# MCU.net
KiCad netlist of a schematic drawn in Altium Designer
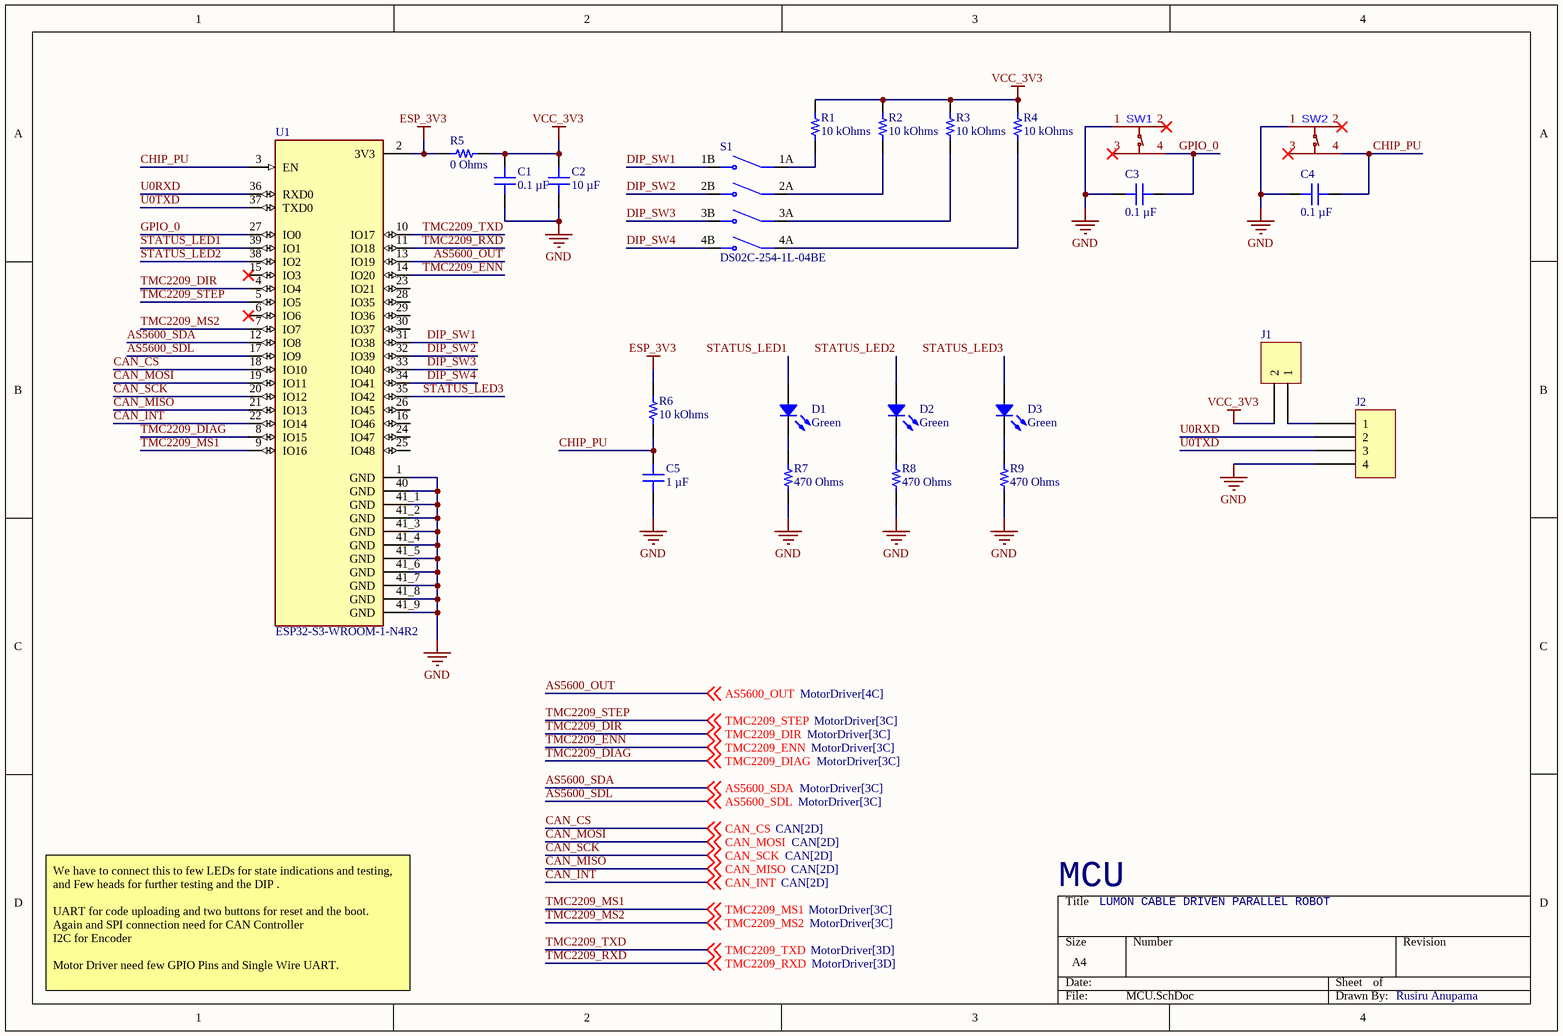
[diagram p0: MCU.SchDoc]

(export (version "E")
  (design (tool "Eeschema 10.0.6"))
  (components
    (comp (ref "C1")
      (value "0.1 µF")
      (footprint "CAP 0805_2012")
      (description "CAP CER 0.1UF 50V X7R 0805")
      (fields
        (field (name "PART NUMBER") "CC0805MRX7R9BB104")
        (field (name "CAPACITANCE") "0.1 µF")
        (field (name "MANUFACTURER") "Yageo")
      )
      (libsource (lib "Celestial Altium Library - altium_library") (part "Capacitor"))
    )
    (comp (ref "C2")
      (value "10 µF")
      (footprint "CAP 0805_2012")
      (description "CAP CER 10UF 10V X7S 0805")
      (fields
        (field (name "PART NUMBER") "CL21Y106KPQVPNE")
        (field (name "CAPACITANCE") "10 µF")
        (field (name "MANUFACTURER") "Samsung Electro-Mechanics")
      )
      (libsource (lib "Celestial Altium Library - altium_library") (part "Capacitor"))
    )
    (comp (ref "C3")
      (value "0.1 µF")
      (footprint "CAP 0805_2012")
      (description "CAP CER 0.1UF 50V X7R 0805")
      (fields
        (field (name "PART NUMBER") "CC0805MRX7R9BB104")
        (field (name "CAPACITANCE") "0.1 µF")
        (field (name "MANUFACTURER") "Yageo")
      )
      (libsource (lib "Celestial Altium Library - altium_library") (part "Capacitor"))
    )
    (comp (ref "C4")
      (value "0.1 µF")
      (footprint "CAP 0805_2012")
      (description "CAP CER 0.1UF 50V X7R 0805")
      (fields
        (field (name "PART NUMBER") "CC0805MRX7R9BB104")
        (field (name "CAPACITANCE") "0.1 µF")
        (field (name "MANUFACTURER") "Yageo")
      )
      (libsource (lib "Celestial Altium Library - altium_library") (part "Capacitor"))
    )
    (comp (ref "C5")
      (value "1 µF")
      (footprint "CAP 0805_2012")
      (description "CAP CER 1UF 16V X8R 0805")
      (fields
        (field (name "PART NUMBER") "C2012X8R1C105K125AB")
        (field (name "CAPACITANCE") "1 µF")
        (field (name "MANUFACTURER") "TDK Corporation")
      )
      (libsource (lib "Celestial Altium Library - altium_library") (part "Capacitor"))
    )
    (comp (ref "D1")
      (value "Green")
      (footprint "LED 0805_2012 GREEN")
      (description "LED GREEN 0805 SMD")
      (fields (field (name "PART NUMBER") "5975316507F") (field (name "MANUFACTURER") "Dialight"))
      (libsource (lib "Celestial Altium Library - altium_library") (part "LED"))
    )
    (comp (ref "D2")
      (value "Green")
      (footprint "LED 0805_2012 GREEN")
      (description "LED GREEN 0805 SMD")
      (fields (field (name "PART NUMBER") "5975316507F") (field (name "MANUFACTURER") "Dialight"))
      (libsource (lib "Celestial Altium Library - altium_library") (part "LED"))
    )
    (comp (ref "D3")
      (value "Green")
      (footprint "LED 0805_2012 GREEN")
      (description "LED GREEN 0805 SMD")
      (fields (field (name "PART NUMBER") "5975316507F") (field (name "MANUFACTURER") "Dialight"))
      (libsource (lib "Celestial Altium Library - altium_library") (part "LED"))
    )
    (comp (ref "J1")
      (value "0022272021")
      (footprint "MOLEX KK 0022272021")
      (description "CONN HEADER VERT 2POS 2.54MM")
      (fields (field (name "MANUFACTURER") "Molex"))
      (libsource (lib "Celestial Altium Library - altium_library") (part "2 Pin"))
    )
    (comp (ref "J2")
      (value "0022272041")
      (footprint "MOLEX KK 0022272041")
      (description "CONN HEADER VERT 4POS 2.54MM")
      (fields (field (name "MANUFACTURER") "Molex"))
      (libsource (lib "Celestial Altium Library - altium_library") (part "4 Pin"))
    )
    (comp (ref "R1")
      (value "10 kOhms")
      (footprint "RES 0805_2012")
      (description "RES SMD 10K OHM 0.1% 1/10W 0805")
      (fields
        (field (name "PART NUMBER") "CPF0805B10KE")
        (field (name "MANUFACTURER") "TE Connectivity Passive Product")
      )
      (libsource (lib "Celestial Altium Library - altium_library") (part "Resistor"))
    )
    (comp (ref "R2")
      (value "10 kOhms")
      (footprint "RES 0805_2012")
      (description "RES SMD 10K OHM 0.1% 1/10W 0805")
      (fields
        (field (name "PART NUMBER") "CPF0805B10KE")
        (field (name "MANUFACTURER") "TE Connectivity Passive Product")
      )
      (libsource (lib "Celestial Altium Library - altium_library") (part "Resistor"))
    )
    (comp (ref "R3")
      (value "10 kOhms")
      (footprint "RES 0805_2012")
      (description "RES SMD 10K OHM 0.1% 1/10W 0805")
      (fields
        (field (name "PART NUMBER") "CPF0805B10KE")
        (field (name "MANUFACTURER") "TE Connectivity Passive Product")
      )
      (libsource (lib "Celestial Altium Library - altium_library") (part "Resistor"))
    )
    (comp (ref "R4")
      (value "10 kOhms")
      (footprint "RES 0805_2012")
      (description "RES SMD 10K OHM 0.1% 1/10W 0805")
      (fields
        (field (name "PART NUMBER") "CPF0805B10KE")
        (field (name "MANUFACTURER") "TE Connectivity Passive Product")
      )
      (libsource (lib "Celestial Altium Library - altium_library") (part "Resistor"))
    )
    (comp (ref "R5")
      (value "0 Ohms")
      (footprint "RES 0805_2012")
      (description "RES 0 OHM JUMPER 0805")
      (fields
        (field (name "PART NUMBER") "TLRZ2ATTD")
        (field (name "MANUFACTURER") "KOA Speer Electronics, Inc.")
      )
      (libsource (lib "Celestial Altium Library - altium_library") (part "Resistor"))
    )
    (comp (ref "R6")
      (value "10 kOhms")
      (footprint "RES 0805_2012")
      (description "RES SMD 10K OHM 0.1% 1/10W 0805")
      (fields
        (field (name "PART NUMBER") "CPF0805B10KE")
        (field (name "MANUFACTURER") "TE Connectivity Passive Product")
      )
      (libsource (lib "Celestial Altium Library - altium_library") (part "Resistor"))
    )
    (comp (ref "R7")
      (value "470 Ohms")
      (footprint "RES 0805_2012")
      (description "RES SMD 470 OHM 0.1% 1/4W 0805")
      (fields
        (field (name "PART NUMBER") "ERJ-PB6B4700V")
        (field (name "MANUFACTURER") "Panasonic Electronic Components")
      )
      (libsource (lib "Celestial Altium Library - altium_library") (part "Resistor"))
    )
    (comp (ref "R8")
      (value "470 Ohms")
      (footprint "RES 0805_2012")
      (description "RES SMD 470 OHM 0.1% 1/4W 0805")
      (fields
        (field (name "PART NUMBER") "ERJ-PB6B4700V")
        (field (name "MANUFACTURER") "Panasonic Electronic Components")
      )
      (libsource (lib "Celestial Altium Library - altium_library") (part "Resistor"))
    )
    (comp (ref "R9")
      (value "470 Ohms")
      (footprint "RES 0805_2012")
      (description "RES SMD 470 OHM 0.1% 1/4W 0805")
      (fields
        (field (name "PART NUMBER") "ERJ-PB6B4700V")
        (field (name "MANUFACTURER") "Panasonic Electronic Components")
      )
      (libsource (lib "Celestial Altium Library - altium_library") (part "Resistor"))
    )
    (comp (ref "S1")
      (value "DS02C-254-1L-04BE")
      (footprint "SW_DS02C-254-1L-04BE")
      (fields (field (name "MF") "Same Sky") (field (name "LCSC PART #") "C5123702"))
      (libsource (lib "Actuator Lib") (part "DS02C-254-1L-04BE"))
    )
    (comp (ref "SW1")
      (value "4.5X4.5X5.0WATERPROOF TACT SWITCH DIP 260G")
      (footprint "SW-TH_4P-L4.5-W4.5-P3.00-LS5.5")
      (fields (field (name "LCSC PART #") "C39832249"))
      (libsource (lib "Actuator Lib") (part "4.5X4.5X5.0WATERPROOF TACT SWITCH DIP 260G"))
    )
    (comp (ref "SW2")
      (value "4.5X4.5X5.0WATERPROOF TACT SWITCH DIP 260G")
      (footprint "SW-TH_4P-L4.5-W4.5-P3.00-LS5.5")
      (fields (field (name "LCSC PART #") "C39832249"))
      (libsource (lib "Actuator Lib") (part "4.5X4.5X5.0WATERPROOF TACT SWITCH DIP 260G"))
    )
    (comp (ref "U1")
      (value "ESP32-S3-WROOM-1-N4R2")
      (footprint "XCVR_ESP32-S3-WROOM-1-N4R2")
      (description "Bluetooth, WiFi 802.11b/g/n, Bluetooth v5.0 Transceiver Module 2.4GHz PCB Trace Surface Mount")
      (fields (field (name "MF") "Espressif Systems") (field (name "LCSC PART #") "C82899"))
      (libsource (lib "Actuator Lib") (part "ESP32-S3-WROOM-1-N4R2"))
    )
  )
  (nets
    (net (code "1") (name "/CHIP_PU") (class "Default")
      (node (ref "C4") (pin "2") (pinfunction "2_2") (pintype "passive"))
      (node (ref "C5") (pin "2") (pinfunction "2_2") (pintype "passive"))
      (node (ref "R6") (pin "1") (pinfunction "1_1") (pintype "passive"))
      (node (ref "SW2") (pin "4") (pinfunction "D_4") (pintype "passive"))
      (node (ref "U1") (pin "3") (pinfunction "EN_3") (pintype "input"))
    )
    (net (code "2") (name "/DIP_SW1") (class "Default")
      (node (ref "S1") (pin "1B") (pinfunction "NO1_1B") (pintype "passive"))
      (node (ref "U1") (pin "31") (pinfunction "IO38_31") (pintype "bidirectional"))
    )
    (net (code "3") (name "/DIP_SW2") (class "Default")
      (node (ref "S1") (pin "2B") (pinfunction "NO2_2B") (pintype "passive"))
      (node (ref "U1") (pin "32") (pinfunction "IO39_32") (pintype "bidirectional"))
    )
    (net (code "4") (name "/DIP_SW3") (class "Default")
      (node (ref "S1") (pin "3B") (pinfunction "NO3_3B") (pintype "passive"))
      (node (ref "U1") (pin "33") (pinfunction "IO40_33") (pintype "bidirectional"))
    )
    (net (code "5") (name "/DIP_SW4") (class "Default")
      (node (ref "S1") (pin "4B") (pinfunction "NO4_4B") (pintype "passive"))
      (node (ref "U1") (pin "34") (pinfunction "IO41_34") (pintype "bidirectional"))
    )
    (net (code "6") (name "/GPIO_0") (class "Default")
      (node (ref "C3") (pin "2") (pinfunction "2_2") (pintype "passive"))
      (node (ref "SW1") (pin "4") (pinfunction "D_4") (pintype "passive"))
      (node (ref "U1") (pin "27") (pinfunction "IO0_27") (pintype "bidirectional"))
    )
    (net (code "7") (name "/STATUS_LED1") (class "Default")
      (node (ref "D1") (pin "1") (pinfunction "1_1") (pintype "passive"))
      (node (ref "U1") (pin "39") (pinfunction "IO1_39") (pintype "bidirectional"))
    )
    (net (code "8") (name "/STATUS_LED2") (class "Default")
      (node (ref "D2") (pin "1") (pinfunction "1_1") (pintype "passive"))
      (node (ref "U1") (pin "38") (pinfunction "IO2_38") (pintype "bidirectional"))
    )
    (net (code "9") (name "/STATUS_LED3") (class "Default")
      (node (ref "D3") (pin "1") (pinfunction "1_1") (pintype "passive"))
      (node (ref "U1") (pin "35") (pinfunction "IO42_35") (pintype "bidirectional"))
    )
    (net (code "10") (name "/U0RXD") (class "Default")
      (node (ref "J2") (pin "2") (pinfunction "2_2") (pintype "passive"))
      (node (ref "U1") (pin "36") (pinfunction "RXD0_36") (pintype "bidirectional"))
    )
    (net (code "11") (name "/U0TXD") (class "Default")
      (node (ref "J2") (pin "3") (pinfunction "3_3") (pintype "passive"))
      (node (ref "U1") (pin "37") (pinfunction "TXD0_37") (pintype "bidirectional"))
    )
    (net (code "12") (name "AS5600_OUT") (class "Default")
      (node (ref "U1") (pin "13") (pinfunction "IO19_13") (pintype "bidirectional"))
    )
    (net (code "13") (name "AS5600_SDA") (class "Default")
      (node (ref "U1") (pin "12") (pinfunction "IO8_12") (pintype "bidirectional"))
    )
    (net (code "14") (name "AS5600_SDL") (class "Default")
      (node (ref "U1") (pin "17") (pinfunction "IO9_17") (pintype "bidirectional"))
    )
    (net (code "15") (name "CAN_CS") (class "Default")
      (node (ref "U1") (pin "18") (pinfunction "IO10_18") (pintype "bidirectional"))
    )
    (net (code "16") (name "CAN_INT") (class "Default")
      (node (ref "U1") (pin "22") (pinfunction "IO14_22") (pintype "bidirectional"))
    )
    (net (code "17") (name "CAN_MISO") (class "Default")
      (node (ref "U1") (pin "21") (pinfunction "IO13_21") (pintype "bidirectional"))
    )
    (net (code "18") (name "CAN_MOSI") (class "Default")
      (node (ref "U1") (pin "19") (pinfunction "IO11_19") (pintype "bidirectional"))
    )
    (net (code "19") (name "CAN_SCK") (class "Default")
      (node (ref "U1") (pin "20") (pinfunction "IO12_20") (pintype "bidirectional"))
    )
    (net (code "20") (name "ESP_3V3") (class "Default")
      (node (ref "R5") (pin "1") (pinfunction "1_1") (pintype "passive"))
      (node (ref "R6") (pin "2") (pinfunction "2_2") (pintype "passive"))
      (node (ref "U1") (pin "2") (pinfunction "3V3_2") (pintype "power_in"))
    )
    (net (code "21") (name "GND") (class "Default")
      (node (ref "C1") (pin "1") (pinfunction "1_1") (pintype "passive"))
      (node (ref "C2") (pin "1") (pinfunction "1_1") (pintype "passive"))
      (node (ref "C3") (pin "1") (pinfunction "1_1") (pintype "passive"))
      (node (ref "C4") (pin "1") (pinfunction "1_1") (pintype "passive"))
      (node (ref "C5") (pin "1") (pinfunction "1_1") (pintype "passive"))
      (node (ref "J2") (pin "4") (pinfunction "4_4") (pintype "passive"))
      (node (ref "R7") (pin "1") (pinfunction "1_1") (pintype "passive"))
      (node (ref "R8") (pin "1") (pinfunction "1_1") (pintype "passive"))
      (node (ref "R9") (pin "1") (pinfunction "1_1") (pintype "passive"))
      (node (ref "SW1") (pin "1") (pinfunction "A_1") (pintype "passive"))
      (node (ref "SW2") (pin "1") (pinfunction "A_1") (pintype "passive"))
      (node (ref "U1") (pin "1") (pinfunction "GND_1") (pintype "power_in"))
      (node (ref "U1") (pin "40") (pinfunction "GND_40") (pintype "power_in"))
      (node (ref "U1") (pin "41_1") (pinfunction "GND_41_1") (pintype "power_in"))
      (node (ref "U1") (pin "41_2") (pinfunction "GND_41_2") (pintype "power_in"))
      (node (ref "U1") (pin "41_3") (pinfunction "GND_41_3") (pintype "power_in"))
      (node (ref "U1") (pin "41_4") (pinfunction "GND_41_4") (pintype "power_in"))
      (node (ref "U1") (pin "41_5") (pinfunction "GND_41_5") (pintype "power_in"))
      (node (ref "U1") (pin "41_6") (pinfunction "GND_41_6") (pintype "power_in"))
      (node (ref "U1") (pin "41_7") (pinfunction "GND_41_7") (pintype "power_in"))
      (node (ref "U1") (pin "41_8") (pinfunction "GND_41_8") (pintype "power_in"))
      (node (ref "U1") (pin "41_9") (pinfunction "GND_41_9") (pintype "power_in"))
    )
    (net (code "22") (name "Net-(D1-Pad2)") (class "Default")
      (node (ref "D1") (pin "2") (pinfunction "2_2") (pintype "passive"))
      (node (ref "R7") (pin "2") (pinfunction "2_2") (pintype "passive"))
    )
    (net (code "23") (name "Net-(D2-Pad2)") (class "Default")
      (node (ref "D2") (pin "2") (pinfunction "2_2") (pintype "passive"))
      (node (ref "R8") (pin "2") (pinfunction "2_2") (pintype "passive"))
    )
    (net (code "24") (name "Net-(D3-Pad2)") (class "Default")
      (node (ref "D3") (pin "2") (pinfunction "2_2") (pintype "passive"))
      (node (ref "R9") (pin "2") (pinfunction "2_2") (pintype "passive"))
    )
    (net (code "25") (name "Net-(J1-Pad1)") (class "Default")
      (node (ref "J1") (pin "1") (pinfunction "1_1") (pintype "passive"))
      (node (ref "J2") (pin "1") (pinfunction "1_1") (pintype "passive"))
    )
    (net (code "26") (name "Net-(S1-COM1)") (class "Default")
      (node (ref "R1") (pin "1") (pinfunction "1_1") (pintype "passive"))
      (node (ref "S1") (pin "1A") (pinfunction "COM1_1A") (pintype "passive"))
    )
    (net (code "27") (name "Net-(S1-COM2)") (class "Default")
      (node (ref "R2") (pin "1") (pinfunction "1_1") (pintype "passive"))
      (node (ref "S1") (pin "2A") (pinfunction "COM2_2A") (pintype "passive"))
    )
    (net (code "28") (name "Net-(S1-COM3)") (class "Default")
      (node (ref "R3") (pin "1") (pinfunction "1_1") (pintype "passive"))
      (node (ref "S1") (pin "3A") (pinfunction "COM3_3A") (pintype "passive"))
    )
    (net (code "29") (name "Net-(S1-COM4)") (class "Default")
      (node (ref "R4") (pin "1") (pinfunction "1_1") (pintype "passive"))
      (node (ref "S1") (pin "4A") (pinfunction "COM4_4A") (pintype "passive"))
    )
    (net (code "30") (name "TMC2209_DIAG") (class "Default")
      (node (ref "U1") (pin "8") (pinfunction "IO15_8") (pintype "bidirectional"))
    )
    (net (code "31") (name "TMC2209_DIR") (class "Default")
      (node (ref "U1") (pin "4") (pinfunction "IO4_4") (pintype "bidirectional"))
    )
    (net (code "32") (name "TMC2209_ENN") (class "Default")
      (node (ref "U1") (pin "14") (pinfunction "IO20_14") (pintype "bidirectional"))
    )
    (net (code "33") (name "TMC2209_MS1") (class "Default")
      (node (ref "U1") (pin "9") (pinfunction "IO16_9") (pintype "bidirectional"))
    )
    (net (code "34") (name "TMC2209_MS2") (class "Default")
      (node (ref "U1") (pin "7") (pinfunction "IO7_7") (pintype "bidirectional"))
    )
    (net (code "35") (name "TMC2209_RXD") (class "Default")
      (node (ref "U1") (pin "11") (pinfunction "IO18_11") (pintype "bidirectional"))
    )
    (net (code "36") (name "TMC2209_STEP") (class "Default")
      (node (ref "U1") (pin "5") (pinfunction "IO5_5") (pintype "bidirectional"))
    )
    (net (code "37") (name "TMC2209_TXD") (class "Default")
      (node (ref "U1") (pin "10") (pinfunction "IO17_10") (pintype "bidirectional"))
    )
    (net (code "38") (name "VCC_3V3") (class "Default")
      (node (ref "C1") (pin "2") (pinfunction "2_2") (pintype "passive"))
      (node (ref "C2") (pin "2") (pinfunction "2_2") (pintype "passive"))
      (node (ref "J1") (pin "2") (pinfunction "2_2") (pintype "passive"))
      (node (ref "R1") (pin "2") (pinfunction "2_2") (pintype "passive"))
      (node (ref "R2") (pin "2") (pinfunction "2_2") (pintype "passive"))
      (node (ref "R3") (pin "2") (pinfunction "2_2") (pintype "passive"))
      (node (ref "R4") (pin "2") (pinfunction "2_2") (pintype "passive"))
      (node (ref "R5") (pin "2") (pinfunction "2_2") (pintype "passive"))
    )
    (net (code "39") (name "unconnected-(SW1-B-Pad2)") (class "Default")
      (node (ref "SW1") (pin "2") (pinfunction "B_2") (pintype "passive+no_connect"))
    )
    (net (code "40") (name "unconnected-(SW1-C-Pad3)") (class "Default")
      (node (ref "SW1") (pin "3") (pinfunction "C_3") (pintype "passive+no_connect"))
    )
    (net (code "41") (name "unconnected-(SW2-B-Pad2)") (class "Default")
      (node (ref "SW2") (pin "2") (pinfunction "B_2") (pintype "passive+no_connect"))
    )
    (net (code "42") (name "unconnected-(SW2-C-Pad3)") (class "Default")
      (node (ref "SW2") (pin "3") (pinfunction "C_3") (pintype "passive+no_connect"))
    )
    (net (code "43") (name "unconnected-(U1-IO3-Pad15)") (class "Default")
      (node (ref "U1") (pin "15") (pinfunction "IO3_15") (pintype "bidirectional+no_connect"))
    )
    (net (code "44") (name "unconnected-(U1-IO6-Pad6)") (class "Default")
      (node (ref "U1") (pin "6") (pinfunction "IO6_6") (pintype "bidirectional+no_connect"))
    )
    (net (code "45") (name "unconnected-(U1-IO21-Pad23)") (class "Default")
      (node (ref "U1") (pin "23") (pinfunction "IO21_23") (pintype "bidirectional"))
    )
    (net (code "46") (name "unconnected-(U1-IO35-Pad28)") (class "Default")
      (node (ref "U1") (pin "28") (pinfunction "IO35_28") (pintype "bidirectional"))
    )
    (net (code "47") (name "unconnected-(U1-IO36-Pad29)") (class "Default")
      (node (ref "U1") (pin "29") (pinfunction "IO36_29") (pintype "bidirectional"))
    )
    (net (code "48") (name "unconnected-(U1-IO37-Pad30)") (class "Default")
      (node (ref "U1") (pin "30") (pinfunction "IO37_30") (pintype "bidirectional"))
    )
    (net (code "49") (name "unconnected-(U1-IO45-Pad26)") (class "Default")
      (node (ref "U1") (pin "26") (pinfunction "IO45_26") (pintype "bidirectional"))
    )
    (net (code "50") (name "unconnected-(U1-IO46-Pad16)") (class "Default")
      (node (ref "U1") (pin "16") (pinfunction "IO46_16") (pintype "bidirectional"))
    )
    (net (code "51") (name "unconnected-(U1-IO47-Pad24)") (class "Default")
      (node (ref "U1") (pin "24") (pinfunction "IO47_24") (pintype "bidirectional"))
    )
    (net (code "52") (name "unconnected-(U1-IO48-Pad25)") (class "Default")
      (node (ref "U1") (pin "25") (pinfunction "IO48_25") (pintype "bidirectional"))
    )
  )
)
